# TSOC_GROVEY_GPIO.net
KiCad netlist of a schematic drawn in EAGLE
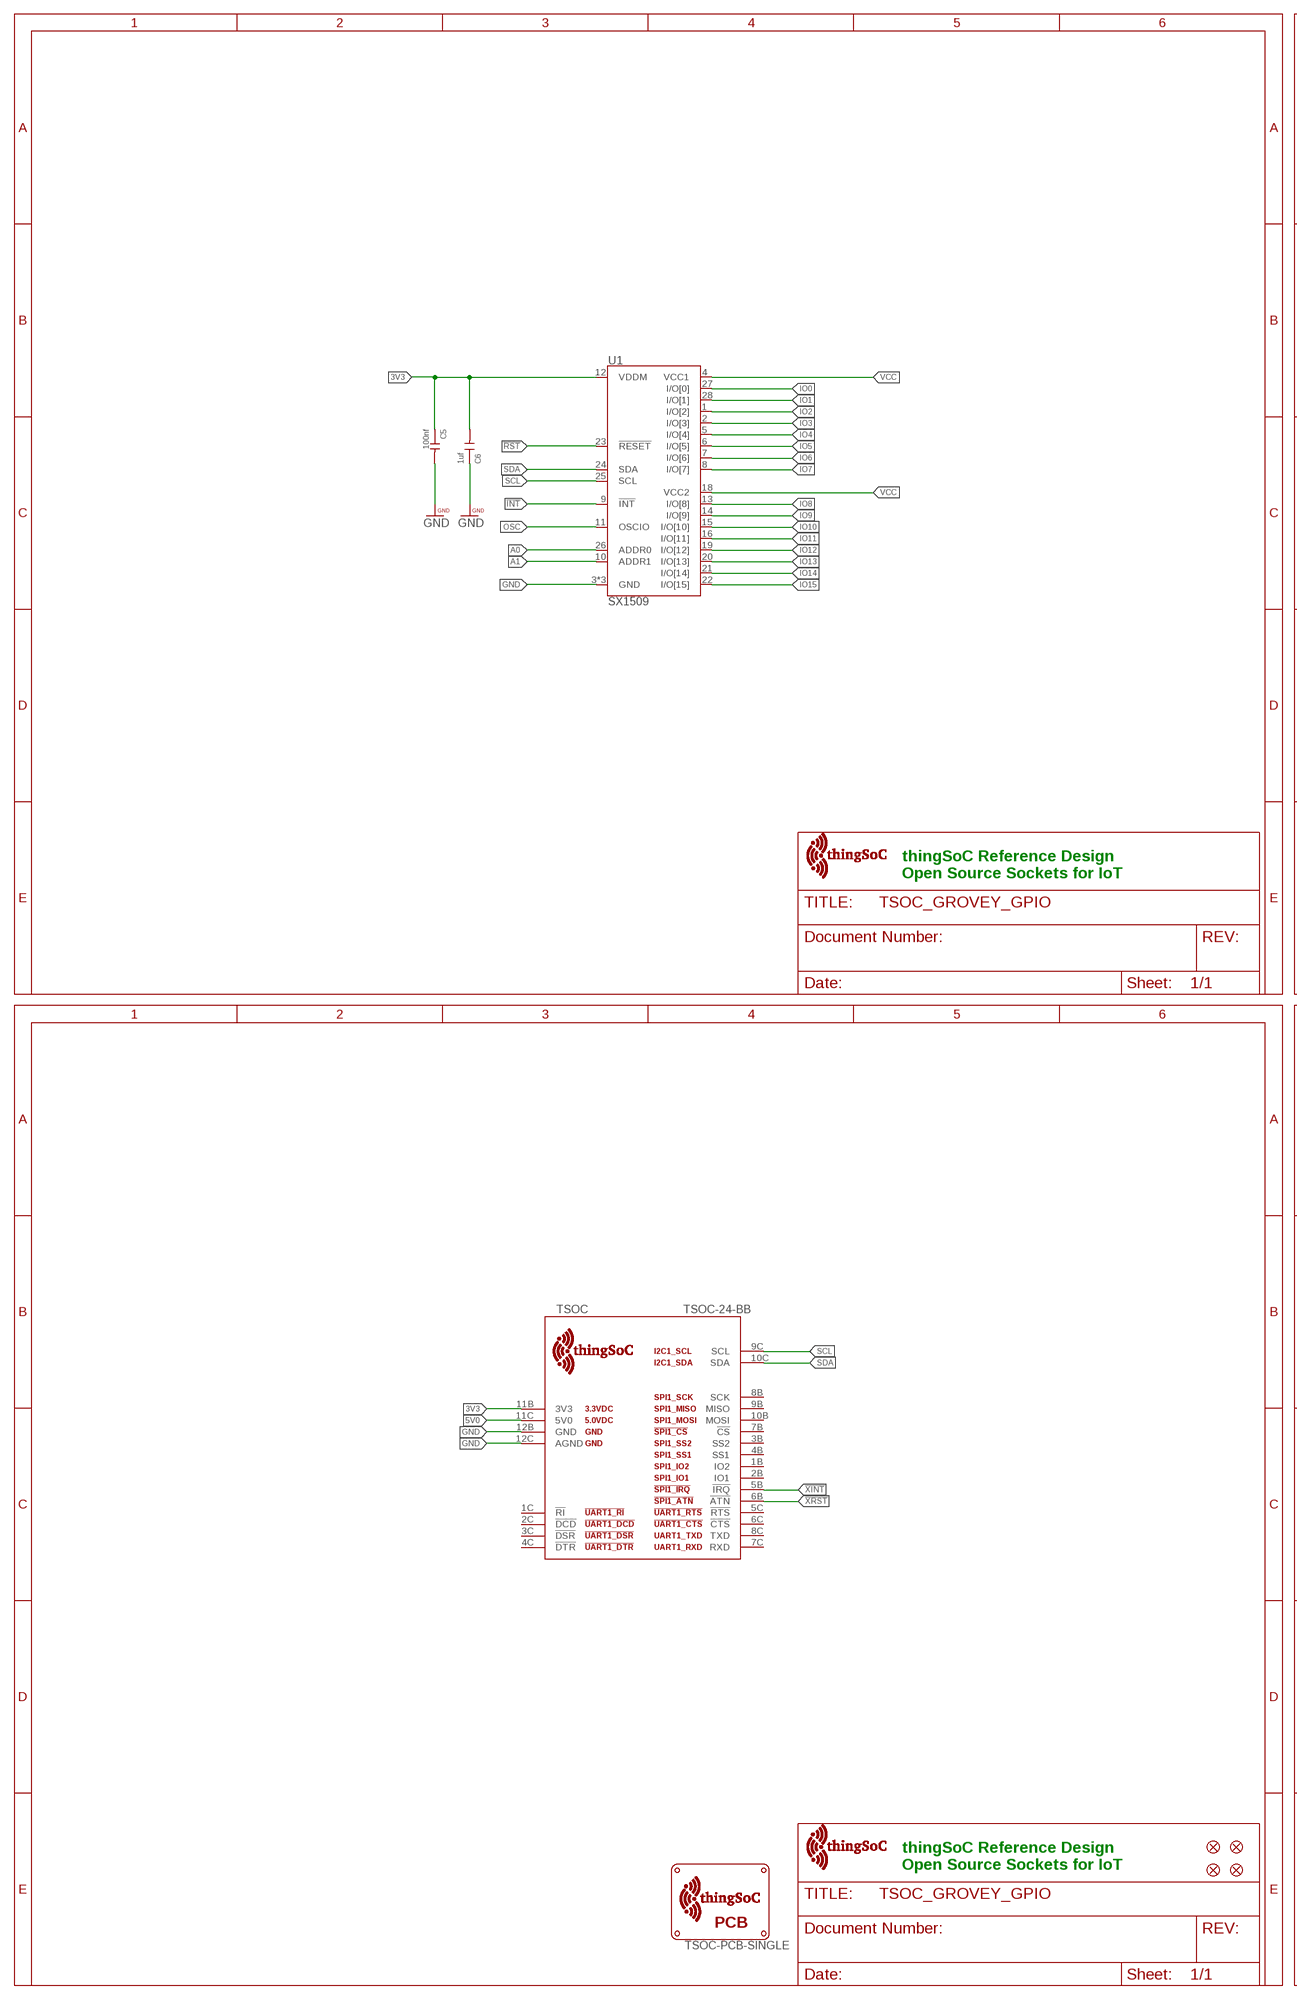
[diagram p0: schematic, sheet 1, part 1 of 2]
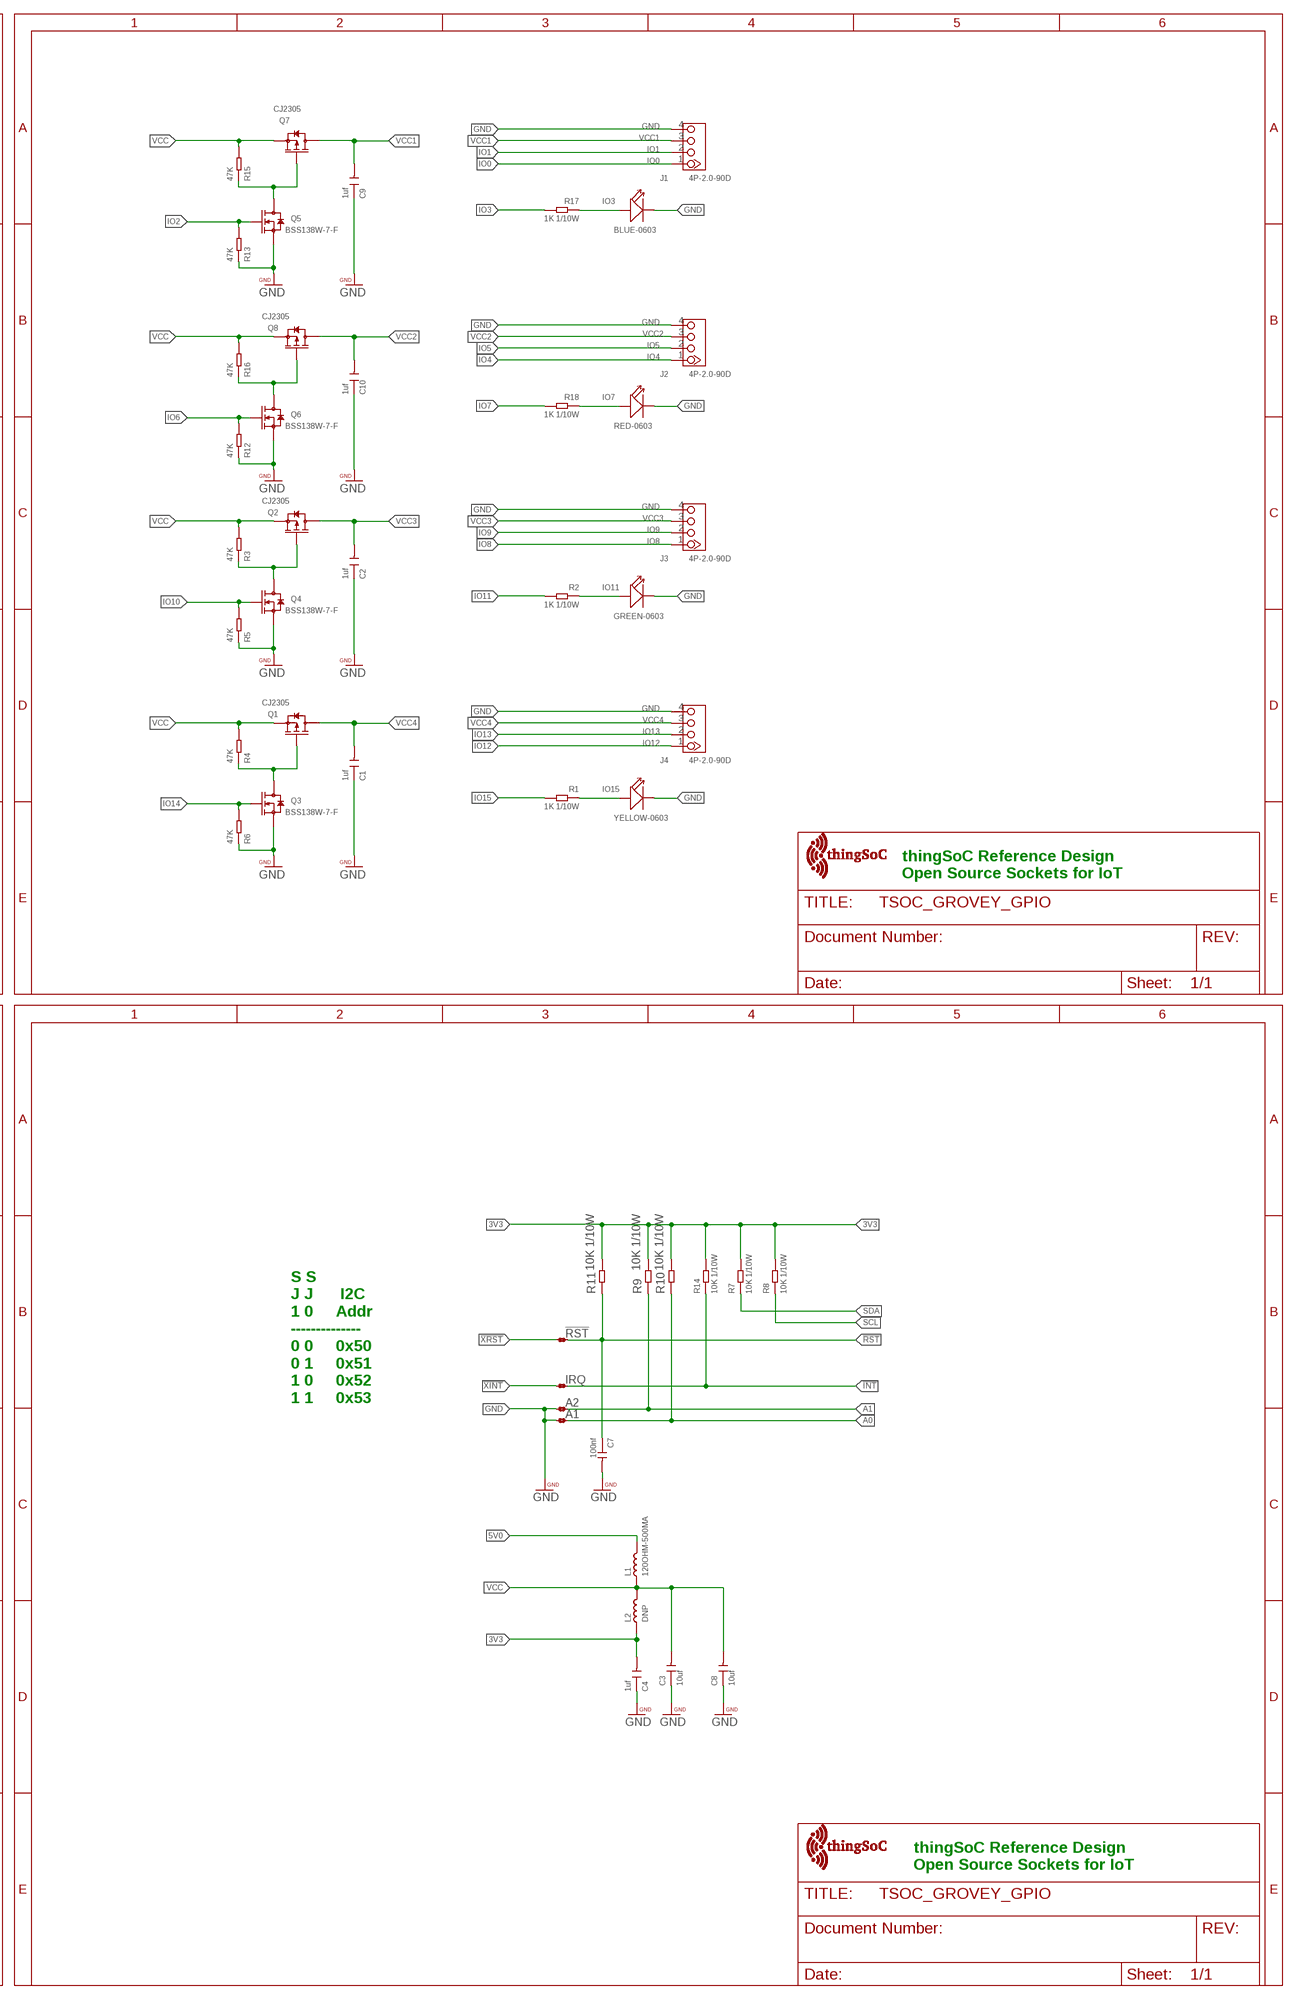
[diagram p1: schematic, sheet 1, part 2 of 2]

(export (version "E")
  (design (tool "Eeschema 10.0.6"))
  (components
    (comp (ref "!RST")
      (value "NO")
      (footprint "eagle-import:JMP-2-NO")
      (libsource (lib "eagle-import") (part "JMP-2-NO"))
    )
    (comp (ref "$$U$1")
      (value "TSOC-LOGO-SMALL")
      (footprint "eagle-import:TSOC-LOGO-SML")
      (libsource (lib "eagle-import") (part "TSOC-LOGO-SMALL"))
    )
    (comp (ref "$$U$2")
      (value "TSOC-LOGO-SMALL")
      (footprint "eagle-import:TSOC-LOGO-SML")
      (libsource (lib "eagle-import") (part "TSOC-LOGO-SMALL"))
    )
    (comp (ref "A1")
      (value "NO")
      (footprint "eagle-import:JMP-2-NO")
      (libsource (lib "eagle-import") (part "JMP-2-NO"))
    )
    (comp (ref "A2")
      (value "NO")
      (footprint "eagle-import:JMP-2-NO")
      (libsource (lib "eagle-import") (part "JMP-2-NO"))
    )
    (comp (ref "C1")
      (value "1uf")
      (footprint "eagle-import:C0603")
      (fields (field (name "MPN") "CC0603KRX7R8BB105"))
      (libsource (lib "eagle-import") (part "CERAMIC-1UF-25V-10%-X7R(0603)"))
    )
    (comp (ref "C2")
      (value "1uf")
      (footprint "eagle-import:C0603")
      (fields (field (name "MPN") "CC0603KRX7R8BB105"))
      (libsource (lib "eagle-import") (part "CERAMIC-1UF-25V-10%-X7R(0603)"))
    )
    (comp (ref "C3")
      (value "10uf")
      (footprint "eagle-import:C1206")
      (fields (field (name "MPN") "CC1206KKX5R8BB106"))
      (libsource (lib "eagle-import") (part "CERAMIC-10UF-25V-10%-X5R(1206)"))
    )
    (comp (ref "C4")
      (value "1uf")
      (footprint "eagle-import:C0603")
      (fields (field (name "MPN") "CC0603KRX7R8BB105"))
      (libsource (lib "eagle-import") (part "CERAMIC-1UF-25V-10%-X7R(0603)"))
    )
    (comp (ref "C5")
      (value "100nf")
      (footprint "eagle-import:C0603")
      (fields (field (name "MPN") "CC0603KRX7R9BB104"))
      (libsource (lib "eagle-import") (part "CERAMIC-100NF-50V-10%-X7R(0603)"))
    )
    (comp (ref "C6")
      (value "1uf")
      (footprint "eagle-import:C0603")
      (fields (field (name "MPN") "CC0603KRX7R8BB105"))
      (libsource (lib "eagle-import") (part "CERAMIC-1UF-25V-10%-X7R(0603)"))
    )
    (comp (ref "C7")
      (value "100nf")
      (footprint "eagle-import:C0603")
      (fields (field (name "MPN") "CC0603KRX7R9BB104"))
      (libsource (lib "eagle-import") (part "CERAMIC-100NF-50V-10%-X7R(0603)"))
    )
    (comp (ref "C8")
      (value "10uf")
      (footprint "eagle-import:C1206")
      (fields (field (name "MPN") "CC1206KKX5R8BB106"))
      (libsource (lib "eagle-import") (part "CERAMIC-10UF-25V-10%-X5R(1206)"))
    )
    (comp (ref "C9")
      (value "1uf")
      (footprint "eagle-import:C0603")
      (fields (field (name "MPN") "CC0603KRX7R8BB105"))
      (libsource (lib "eagle-import") (part "CERAMIC-1UF-25V-10%-X7R(0603)"))
    )
    (comp (ref "C10")
      (value "1uf")
      (footprint "eagle-import:C0603")
      (fields (field (name "MPN") "CC0603KRX7R8BB105"))
      (libsource (lib "eagle-import") (part "CERAMIC-1UF-25V-10%-X7R(0603)"))
    )
    (comp (ref "FID1")
      (value "FIDUCIALUFIDUCIAL")
      (footprint "eagle-import:MICRO-FIDUCIAL")
      (libsource (lib "eagle-import") (part "FIDUCIALUFIDUCIAL"))
    )
    (comp (ref "FID2")
      (value "FIDUCIALUFIDUCIAL")
      (footprint "eagle-import:MICRO-FIDUCIAL")
      (libsource (lib "eagle-import") (part "FIDUCIALUFIDUCIAL"))
    )
    (comp (ref "FID3")
      (value "FIDUCIALUFIDUCIAL")
      (footprint "eagle-import:MICRO-FIDUCIAL")
      (libsource (lib "eagle-import") (part "FIDUCIALUFIDUCIAL"))
    )
    (comp (ref "FID4")
      (value "FIDUCIALUFIDUCIAL")
      (footprint "eagle-import:MICRO-FIDUCIAL")
      (libsource (lib "eagle-import") (part "FIDUCIALUFIDUCIAL"))
    )
    (comp (ref "IO3")
      (value "BLUE-0603")
      (footprint "eagle-import:LED-0603")
      (fields (field (name "MPN") "19-217-BHC-ZL1M2RY-3T"))
      (libsource (lib "eagle-import") (part "SMD-LED-CLEAR-BLUE(0603)"))
    )
    (comp (ref "IO7")
      (value "RED-0603")
      (footprint "eagle-import:LED-0603")
      (fields (field (name "MPN") "19-217-R6C-AL1M2VY-3T"))
      (libsource (lib "eagle-import") (part "LED-SMD-RED-DIFFUSED(0603)"))
    )
    (comp (ref "IO11")
      (value "GREEN-0603")
      (footprint "eagle-import:LED-0603")
      (fields (field (name "MPN") "19-217-G7C-AN1P2-3T"))
      (libsource (lib "eagle-import") (part "SMD-LED-CLEAR-GREEN(0603)"))
    )
    (comp (ref "IO15")
      (value "YELLOW-0603")
      (footprint "eagle-import:LED-0603")
      (fields (field (name "MPN") "19-217-Y5C-AM1N1VY-3T"))
      (libsource (lib "eagle-import") (part "SMD-LED-CLEAR-YELLOW(0603)"))
    )
    (comp (ref "IRQ")
      (value "NO")
      (footprint "eagle-import:JMP-2-NO")
      (libsource (lib "eagle-import") (part "JMP-2-NO"))
    )
    (comp (ref "J1")
      (value "4P-2.0-90D")
      (footprint "eagle-import:HW4-2.0-90D")
      (libsource (lib "eagle-import") (part "GROVE-CONNECTOR-DIP-90D(4P-2.0)"))
    )
    (comp (ref "J2")
      (value "4P-2.0-90D")
      (footprint "eagle-import:HW4-2.0-90D")
      (libsource (lib "eagle-import") (part "GROVE-CONNECTOR-DIP-90D(4P-2.0)"))
    )
    (comp (ref "J3")
      (value "4P-2.0-90D")
      (footprint "eagle-import:HW4-2.0-90D")
      (libsource (lib "eagle-import") (part "GROVE-CONNECTOR-DIP-90D(4P-2.0)"))
    )
    (comp (ref "J4")
      (value "4P-2.0-90D")
      (footprint "eagle-import:HW4-2.0-90D")
      (libsource (lib "eagle-import") (part "GROVE-CONNECTOR-DIP-90D(4P-2.0)"))
    )
    (comp (ref "L1")
      (value "120OHM-500MA")
      (footprint "eagle-import:L0603")
      (fields (field (name "MPN") "BLM18AG121SN1D"))
      (libsource (lib "eagle-import") (part "SMD-FERRITE-CHIP-120-OHM-500MA(0603)"))
    )
    (comp (ref "L2")
      (value "DNP")
      (footprint "eagle-import:L0603")
      (fields (field (name "MPN") "BLM18AG121SN1D"))
      (libsource (lib "eagle-import") (part "SMD-FERRITE-CHIP-120-OHM-500MA(0603)"))
    )
    (comp (ref "Q1")
      (value "CJ2305")
      (footprint "eagle-import:SOT-23")
      (libsource (lib "eagle-import") (part "SMD-MOSFET-P-CH-8V-4.1A-CJ2305(SOT-23)"))
    )
    (comp (ref "Q2")
      (value "CJ2305")
      (footprint "eagle-import:SOT-23")
      (libsource (lib "eagle-import") (part "SMD-MOSFET-P-CH-8V-4.1A-CJ2305(SOT-23)"))
    )
    (comp (ref "Q3")
      (value "BSS138W-7-F")
      (footprint "eagle-import:SOT-23")
      (libsource (lib "eagle-import") (part "SMD-MOSFET-N-CH-50V-200MA-BSS138W-7-F(SOT-23)"))
    )
    (comp (ref "Q4")
      (value "BSS138W-7-F")
      (footprint "eagle-import:SOT-23")
      (libsource (lib "eagle-import") (part "SMD-MOSFET-N-CH-50V-200MA-BSS138W-7-F(SOT-23)"))
    )
    (comp (ref "Q5")
      (value "BSS138W-7-F")
      (footprint "eagle-import:SOT-23")
      (libsource (lib "eagle-import") (part "SMD-MOSFET-N-CH-50V-200MA-BSS138W-7-F(SOT-23)"))
    )
    (comp (ref "Q6")
      (value "BSS138W-7-F")
      (footprint "eagle-import:SOT-23")
      (libsource (lib "eagle-import") (part "SMD-MOSFET-N-CH-50V-200MA-BSS138W-7-F(SOT-23)"))
    )
    (comp (ref "Q7")
      (value "CJ2305")
      (footprint "eagle-import:SOT-23")
      (libsource (lib "eagle-import") (part "SMD-MOSFET-P-CH-8V-4.1A-CJ2305(SOT-23)"))
    )
    (comp (ref "Q8")
      (value "CJ2305")
      (footprint "eagle-import:SOT-23")
      (libsource (lib "eagle-import") (part "SMD-MOSFET-P-CH-8V-4.1A-CJ2305(SOT-23)"))
    )
    (comp (ref "R1")
      (value "1K 1/10W")
      (footprint "eagle-import:R0603")
      (fields (field (name "MPN") "RC0603JR-071KL"))
      (libsource (lib "eagle-import") (part "SMD-RES-1K-5%-1/10W(0603)"))
    )
    (comp (ref "R2")
      (value "1K 1/10W")
      (footprint "eagle-import:R0603")
      (fields (field (name "MPN") "RC0603JR-071KL"))
      (libsource (lib "eagle-import") (part "SMD-RES-1K-5%-1/10W(0603)"))
    )
    (comp (ref "R3")
      (value "47K")
      (footprint "eagle-import:R0603")
      (fields (field (name "MPN") "RC0603JR-0747KL"))
      (libsource (lib "eagle-import") (part "SMD-RES-47K-5%-1/10W(0603)"))
    )
    (comp (ref "R4")
      (value "47K")
      (footprint "eagle-import:R0603")
      (fields (field (name "MPN") "RC0603JR-0747KL"))
      (libsource (lib "eagle-import") (part "SMD-RES-47K-5%-1/10W(0603)"))
    )
    (comp (ref "R5")
      (value "47K")
      (footprint "eagle-import:R0603")
      (fields (field (name "MPN") "RC0603JR-0747KL"))
      (libsource (lib "eagle-import") (part "SMD-RES-47K-5%-1/10W(0603)"))
    )
    (comp (ref "R6")
      (value "47K")
      (footprint "eagle-import:R0603")
      (fields (field (name "MPN") "RC0603JR-0747KL"))
      (libsource (lib "eagle-import") (part "SMD-RES-47K-5%-1/10W(0603)"))
    )
    (comp (ref "R7")
      (value "10K 1/10W")
      (footprint "eagle-import:R0603")
      (fields (field (name "MPN") "RC0603JR-0710KL"))
      (libsource (lib "eagle-import") (part "SMD-RES-10K-5%-1/10W(0603)"))
    )
    (comp (ref "R8")
      (value "10K 1/10W")
      (footprint "eagle-import:R0603")
      (fields (field (name "MPN") "RC0603JR-0710KL"))
      (libsource (lib "eagle-import") (part "SMD-RES-10K-5%-1/10W(0603)"))
    )
    (comp (ref "R9")
      (value "10K 1/10W")
      (footprint "eagle-import:R0603")
      (fields (field (name "MPN") "RC0603JR-0710KL"))
      (libsource (lib "eagle-import") (part "SMD-RES-10K-5%-1/10W(0603)"))
    )
    (comp (ref "R10")
      (value "10K 1/10W")
      (footprint "eagle-import:R0603")
      (fields (field (name "MPN") "RC0603JR-0710KL"))
      (libsource (lib "eagle-import") (part "SMD-RES-10K-5%-1/10W(0603)"))
    )
    (comp (ref "R11")
      (value "10K 1/10W")
      (footprint "eagle-import:R0603")
      (fields (field (name "MPN") "RC0603JR-0710KL"))
      (libsource (lib "eagle-import") (part "SMD-RES-10K-5%-1/10W(0603)"))
    )
    (comp (ref "R12")
      (value "47K")
      (footprint "eagle-import:R0603")
      (fields (field (name "MPN") "RC0603JR-0747KL"))
      (libsource (lib "eagle-import") (part "SMD-RES-47K-5%-1/10W(0603)"))
    )
    (comp (ref "R13")
      (value "47K")
      (footprint "eagle-import:R0603")
      (fields (field (name "MPN") "RC0603JR-0747KL"))
      (libsource (lib "eagle-import") (part "SMD-RES-47K-5%-1/10W(0603)"))
    )
    (comp (ref "R14")
      (value "10K 1/10W")
      (footprint "eagle-import:R0603")
      (fields (field (name "MPN") "RC0603JR-0710KL"))
      (libsource (lib "eagle-import") (part "SMD-RES-10K-5%-1/10W(0603)"))
    )
    (comp (ref "R15")
      (value "47K")
      (footprint "eagle-import:R0603")
      (fields (field (name "MPN") "RC0603JR-0747KL"))
      (libsource (lib "eagle-import") (part "SMD-RES-47K-5%-1/10W(0603)"))
    )
    (comp (ref "R16")
      (value "47K")
      (footprint "eagle-import:R0603")
      (fields (field (name "MPN") "RC0603JR-0747KL"))
      (libsource (lib "eagle-import") (part "SMD-RES-47K-5%-1/10W(0603)"))
    )
    (comp (ref "R17")
      (value "1K 1/10W")
      (footprint "eagle-import:R0603")
      (fields (field (name "MPN") "RC0603JR-071KL"))
      (libsource (lib "eagle-import") (part "SMD-RES-1K-5%-1/10W(0603)"))
    )
    (comp (ref "R18")
      (value "1K 1/10W")
      (footprint "eagle-import:R0603")
      (fields (field (name "MPN") "RC0603JR-071KL"))
      (libsource (lib "eagle-import") (part "SMD-RES-1K-5%-1/10W(0603)"))
    )
    (comp (ref "TSOC")
      (value "TSOC-24-BB")
      (footprint "eagle-import:TSOC-BB-S24")
      (libsource (lib "eagle-import") (part "TSOC-24-BB"))
    )
    (comp (ref "U$3")
      (value "TSOC-PCB-SINGLE")
      (footprint "eagle-import:TSOC-BB-BRD-DIM")
      (libsource (lib "eagle-import") (part "TSOC-PCB-SINGLE"))
    )
    (comp (ref "U$101")
      (value "TSOC-LOGO-LRG")
      (footprint "eagle-import:TSOC-LOGO-LRG")
      (libsource (lib "eagle-import") (part "TSOC-LOGO-LRG"))
    )
    (comp (ref "U$102")
      (value "TSOC-LOGO-SMALL")
      (footprint "eagle-import:TSOC-LOGO-SML")
      (libsource (lib "eagle-import") (part "TSOC-LOGO-SMALL"))
    )
    (comp (ref "U1")
      (value "SX1509")
      (footprint "eagle-import:QFN-28")
      (libsource (lib "eagle-import") (part "SX1509"))
    )
  )
  (nets
    (net (code "1") (name "/~{INT}") (class "Default")
      (node (ref "IRQ") (pin "2") (pinfunction "2_2") (pintype "passive"))
      (node (ref "R14") (pin "1") (pinfunction "1_1") (pintype "passive"))
      (node (ref "U1") (pin "9") (pinfunction "~{INT}_9") (pintype "bidirectional"))
    )
    (net (code "2") (name "/~{RST}") (class "Default")
      (node (ref "!RST") (pin "1") (pinfunction "1_1") (pintype "passive"))
      (node (ref "C7") (pin "1") (pinfunction "1_1") (pintype "passive"))
      (node (ref "R11") (pin "1") (pinfunction "1_1") (pintype "passive"))
      (node (ref "U1") (pin "23") (pinfunction "~{RESET}_23") (pintype "bidirectional"))
    )
    (net (code "3") (name "/~{XINT}") (class "Default")
      (node (ref "IRQ") (pin "1") (pinfunction "1_1") (pintype "passive"))
      (node (ref "TSOC") (pin "5B") (pinfunction "~{IRQ}_5B") (pintype "bidirectional"))
    )
    (net (code "4") (name "/~{XRST}") (class "Default")
      (node (ref "!RST") (pin "2") (pinfunction "2_2") (pintype "passive"))
      (node (ref "TSOC") (pin "6B") (pinfunction "~{ATN}_6B") (pintype "bidirectional"))
    )
    (net (code "5") (name "3V3") (class "Default")
      (node (ref "C4") (pin "2") (pinfunction "2_2") (pintype "passive"))
      (node (ref "C5") (pin "1") (pinfunction "1_1") (pintype "passive"))
      (node (ref "C6") (pin "2") (pinfunction "2_2") (pintype "passive"))
      (node (ref "L2") (pin "1") (pinfunction "1_1") (pintype "passive"))
      (node (ref "R10") (pin "2") (pinfunction "2_2") (pintype "passive"))
      (node (ref "R11") (pin "2") (pinfunction "2_2") (pintype "passive"))
      (node (ref "R14") (pin "2") (pinfunction "2_2") (pintype "passive"))
      (node (ref "R7") (pin "2") (pinfunction "2_2") (pintype "passive"))
      (node (ref "R8") (pin "2") (pinfunction "2_2") (pintype "passive"))
      (node (ref "R9") (pin "2") (pinfunction "2_2") (pintype "passive"))
      (node (ref "TSOC") (pin "11B") (pinfunction "3V3_11B") (pintype "bidirectional"))
      (node (ref "U1") (pin "12") (pinfunction "VDDM_12") (pintype "bidirectional"))
    )
    (net (code "6") (name "5V0") (class "Default")
      (node (ref "L1") (pin "2") (pinfunction "2_2") (pintype "passive"))
      (node (ref "TSOC") (pin "11C") (pinfunction "5V0_11C") (pintype "bidirectional"))
    )
    (net (code "7") (name "A0") (class "Default")
      (node (ref "A1") (pin "2") (pinfunction "2_2") (pintype "passive"))
      (node (ref "R10") (pin "1") (pinfunction "1_1") (pintype "passive"))
      (node (ref "U1") (pin "26") (pinfunction "ADDR0_26") (pintype "bidirectional"))
    )
    (net (code "8") (name "A1") (class "Default")
      (node (ref "A2") (pin "2") (pinfunction "2_2") (pintype "passive"))
      (node (ref "R9") (pin "1") (pinfunction "1_1") (pintype "passive"))
      (node (ref "U1") (pin "10") (pinfunction "ADDR1_10") (pintype "bidirectional"))
    )
    (net (code "9") (name "GND") (class "Default")
      (node (ref "A1") (pin "1") (pinfunction "1_1") (pintype "passive"))
      (node (ref "A2") (pin "1") (pinfunction "1_1") (pintype "passive"))
      (node (ref "C1") (pin "1") (pinfunction "1_1") (pintype "passive"))
      (node (ref "C10") (pin "1") (pinfunction "1_1") (pintype "passive"))
      (node (ref "C2") (pin "1") (pinfunction "1_1") (pintype "passive"))
      (node (ref "C3") (pin "1") (pinfunction "1_1") (pintype "passive"))
      (node (ref "C4") (pin "1") (pinfunction "1_1") (pintype "passive"))
      (node (ref "C5") (pin "2") (pinfunction "2_2") (pintype "passive"))
      (node (ref "C6") (pin "1") (pinfunction "1_1") (pintype "passive"))
      (node (ref "C7") (pin "2") (pinfunction "2_2") (pintype "passive"))
      (node (ref "C8") (pin "1") (pinfunction "1_1") (pintype "passive"))
      (node (ref "C9") (pin "1") (pinfunction "1_1") (pintype "passive"))
      (node (ref "IO11") (pin "-") (pinfunction "-_-") (pintype "passive"))
      (node (ref "IO15") (pin "-") (pinfunction "-_-") (pintype "passive"))
      (node (ref "IO3") (pin "-") (pinfunction "-_-") (pintype "passive"))
      (node (ref "IO7") (pin "-") (pinfunction "-_-") (pintype "passive"))
      (node (ref "J1") (pin "4") (pinfunction "4_4") (pintype "bidirectional"))
      (node (ref "J2") (pin "4") (pinfunction "4_4") (pintype "bidirectional"))
      (node (ref "J3") (pin "4") (pinfunction "4_4") (pintype "bidirectional"))
      (node (ref "J4") (pin "4") (pinfunction "4_4") (pintype "bidirectional"))
      (node (ref "Q3") (pin "2") (pinfunction "S_2") (pintype "passive"))
      (node (ref "Q4") (pin "2") (pinfunction "S_2") (pintype "passive"))
      (node (ref "Q5") (pin "2") (pinfunction "S_2") (pintype "passive"))
      (node (ref "Q6") (pin "2") (pinfunction "S_2") (pintype "passive"))
      (node (ref "R12") (pin "1") (pinfunction "1_1") (pintype "passive"))
      (node (ref "R13") (pin "1") (pinfunction "1_1") (pintype "passive"))
      (node (ref "R5") (pin "1") (pinfunction "1_1") (pintype "passive"))
      (node (ref "R6") (pin "1") (pinfunction "1_1") (pintype "passive"))
      (node (ref "TSOC") (pin "12B") (pinfunction "GND_12B") (pintype "bidirectional"))
      (node (ref "TSOC") (pin "12C") (pinfunction "AGND_12C") (pintype "bidirectional"))
      (node (ref "U1") (pin "17") (pinfunction "GND_17") (pintype "bidirectional"))
      (node (ref "U1") (pin "29") (pinfunction "GND_29") (pintype "bidirectional"))
      (node (ref "U1") (pin "3") (pinfunction "GND_3") (pintype "bidirectional"))
    )
    (net (code "10") (name "IO0") (class "Default")
      (node (ref "J1") (pin "1") (pinfunction "1_1") (pintype "bidirectional"))
      (node (ref "U1") (pin "27") (pinfunction "I/O[0]_27") (pintype "bidirectional"))
    )
    (net (code "11") (name "IO1") (class "Default")
      (node (ref "J1") (pin "2") (pinfunction "2_2") (pintype "bidirectional"))
      (node (ref "U1") (pin "28") (pinfunction "I/O[1]_28") (pintype "bidirectional"))
    )
    (net (code "12") (name "IO2") (class "Default")
      (node (ref "Q5") (pin "1") (pinfunction "G_1") (pintype "passive"))
      (node (ref "R13") (pin "2") (pinfunction "2_2") (pintype "passive"))
      (node (ref "U1") (pin "1") (pinfunction "I/O[2]_1") (pintype "bidirectional"))
    )
    (net (code "13") (name "IO3") (class "Default")
      (node (ref "R17") (pin "2") (pinfunction "2_2") (pintype "passive"))
      (node (ref "U1") (pin "2") (pinfunction "I/O[3]_2") (pintype "bidirectional"))
    )
    (net (code "14") (name "IO4") (class "Default")
      (node (ref "J2") (pin "1") (pinfunction "1_1") (pintype "bidirectional"))
      (node (ref "U1") (pin "5") (pinfunction "I/O[4]_5") (pintype "bidirectional"))
    )
    (net (code "15") (name "IO5") (class "Default")
      (node (ref "J2") (pin "2") (pinfunction "2_2") (pintype "bidirectional"))
      (node (ref "U1") (pin "6") (pinfunction "I/O[5]_6") (pintype "bidirectional"))
    )
    (net (code "16") (name "IO6") (class "Default")
      (node (ref "Q6") (pin "1") (pinfunction "G_1") (pintype "passive"))
      (node (ref "R12") (pin "2") (pinfunction "2_2") (pintype "passive"))
      (node (ref "U1") (pin "7") (pinfunction "I/O[6]_7") (pintype "bidirectional"))
    )
    (net (code "17") (name "IO7") (class "Default")
      (node (ref "R18") (pin "2") (pinfunction "2_2") (pintype "passive"))
      (node (ref "U1") (pin "8") (pinfunction "I/O[7]_8") (pintype "bidirectional"))
    )
    (net (code "18") (name "IO8") (class "Default")
      (node (ref "J3") (pin "1") (pinfunction "1_1") (pintype "bidirectional"))
      (node (ref "U1") (pin "13") (pinfunction "I/O[8]_13") (pintype "bidirectional"))
    )
    (net (code "19") (name "IO9") (class "Default")
      (node (ref "J3") (pin "2") (pinfunction "2_2") (pintype "bidirectional"))
      (node (ref "U1") (pin "14") (pinfunction "I/O[9]_14") (pintype "bidirectional"))
    )
    (net (code "20") (name "IO10") (class "Default")
      (node (ref "Q4") (pin "1") (pinfunction "G_1") (pintype "passive"))
      (node (ref "R5") (pin "2") (pinfunction "2_2") (pintype "passive"))
      (node (ref "U1") (pin "15") (pinfunction "I/O[10]_15") (pintype "bidirectional"))
    )
    (net (code "21") (name "IO11") (class "Default")
      (node (ref "R2") (pin "2") (pinfunction "2_2") (pintype "passive"))
      (node (ref "U1") (pin "16") (pinfunction "I/O[11]_16") (pintype "bidirectional"))
    )
    (net (code "22") (name "IO12") (class "Default")
      (node (ref "J4") (pin "1") (pinfunction "1_1") (pintype "bidirectional"))
      (node (ref "U1") (pin "19") (pinfunction "I/O[12]_19") (pintype "bidirectional"))
    )
    (net (code "23") (name "IO13") (class "Default")
      (node (ref "J4") (pin "2") (pinfunction "2_2") (pintype "bidirectional"))
      (node (ref "U1") (pin "20") (pinfunction "I/O[13]_20") (pintype "bidirectional"))
    )
    (net (code "24") (name "IO14") (class "Default")
      (node (ref "Q3") (pin "1") (pinfunction "G_1") (pintype "passive"))
      (node (ref "R6") (pin "2") (pinfunction "2_2") (pintype "passive"))
      (node (ref "U1") (pin "21") (pinfunction "I/O[14]_21") (pintype "bidirectional"))
    )
    (net (code "25") (name "IO15") (class "Default")
      (node (ref "R1") (pin "2") (pinfunction "2_2") (pintype "passive"))
      (node (ref "U1") (pin "22") (pinfunction "I/O[15]_22") (pintype "bidirectional"))
    )
    (net (code "26") (name "Net-(IO3-Pad+)") (class "Default")
      (node (ref "IO3") (pin "+") (pinfunction "+_+") (pintype "passive"))
      (node (ref "R17") (pin "1") (pinfunction "1_1") (pintype "passive"))
    )
    (net (code "27") (name "Net-(IO7-Pad+)") (class "Default")
      (node (ref "IO7") (pin "+") (pinfunction "+_+") (pintype "passive"))
      (node (ref "R18") (pin "1") (pinfunction "1_1") (pintype "passive"))
    )
    (net (code "28") (name "Net-(IO11-Pad+)") (class "Default")
      (node (ref "IO11") (pin "+") (pinfunction "+_+") (pintype "passive"))
      (node (ref "R2") (pin "1") (pinfunction "1_1") (pintype "passive"))
    )
    (net (code "29") (name "Net-(IO15-Pad+)") (class "Default")
      (node (ref "IO15") (pin "+") (pinfunction "+_+") (pintype "passive"))
      (node (ref "R1") (pin "1") (pinfunction "1_1") (pintype "passive"))
    )
    (net (code "30") (name "Net-(Q1-G)") (class "Default")
      (node (ref "Q1") (pin "1") (pinfunction "G_1") (pintype "passive"))
      (node (ref "Q3") (pin "3") (pinfunction "D_3") (pintype "passive"))
      (node (ref "R4") (pin "1") (pinfunction "1_1") (pintype "passive"))
    )
    (net (code "31") (name "Net-(Q2-G)") (class "Default")
      (node (ref "Q2") (pin "1") (pinfunction "G_1") (pintype "passive"))
      (node (ref "Q4") (pin "3") (pinfunction "D_3") (pintype "passive"))
      (node (ref "R3") (pin "1") (pinfunction "1_1") (pintype "passive"))
    )
    (net (code "32") (name "Net-(Q5-D)") (class "Default")
      (node (ref "Q5") (pin "3") (pinfunction "D_3") (pintype "passive"))
      (node (ref "Q7") (pin "1") (pinfunction "G_1") (pintype "passive"))
      (node (ref "R15") (pin "1") (pinfunction "1_1") (pintype "passive"))
    )
    (net (code "33") (name "Net-(Q6-D)") (class "Default")
      (node (ref "Q6") (pin "3") (pinfunction "D_3") (pintype "passive"))
      (node (ref "Q8") (pin "1") (pinfunction "G_1") (pintype "passive"))
      (node (ref "R16") (pin "1") (pinfunction "1_1") (pintype "passive"))
    )
    (net (code "34") (name "OSC") (class "Default")
      (node (ref "U1") (pin "11") (pinfunction "OSCIO_11") (pintype "bidirectional"))
    )
    (net (code "35") (name "SCL") (class "Default")
      (node (ref "R8") (pin "1") (pinfunction "1_1") (pintype "passive"))
      (node (ref "TSOC") (pin "9C") (pinfunction "SCL_9C") (pintype "bidirectional"))
      (node (ref "U1") (pin "25") (pinfunction "SCL_25") (pintype "bidirectional"))
    )
    (net (code "36") (name "SDA") (class "Default")
      (node (ref "R7") (pin "1") (pinfunction "1_1") (pintype "passive"))
      (node (ref "TSOC") (pin "10C") (pinfunction "SDA_10C") (pintype "bidirectional"))
      (node (ref "U1") (pin "24") (pinfunction "SDA_24") (pintype "bidirectional"))
    )
    (net (code "37") (name "VCC") (class "Default")
      (node (ref "C3") (pin "2") (pinfunction "2_2") (pintype "passive"))
      (node (ref "C8") (pin "2") (pinfunction "2_2") (pintype "passive"))
      (node (ref "L1") (pin "1") (pinfunction "1_1") (pintype "passive"))
      (node (ref "L2") (pin "2") (pinfunction "2_2") (pintype "passive"))
      (node (ref "Q1") (pin "2") (pinfunction "S_2") (pintype "passive"))
      (node (ref "Q2") (pin "2") (pinfunction "S_2") (pintype "passive"))
      (node (ref "Q7") (pin "2") (pinfunction "S_2") (pintype "passive"))
      (node (ref "Q8") (pin "2") (pinfunction "S_2") (pintype "passive"))
      (node (ref "R15") (pin "2") (pinfunction "2_2") (pintype "passive"))
      (node (ref "R16") (pin "2") (pinfunction "2_2") (pintype "passive"))
      (node (ref "R3") (pin "2") (pinfunction "2_2") (pintype "passive"))
      (node (ref "R4") (pin "2") (pinfunction "2_2") (pintype "passive"))
      (node (ref "U1") (pin "18") (pinfunction "VCC2_18") (pintype "bidirectional"))
      (node (ref "U1") (pin "4") (pinfunction "VCC1_4") (pintype "bidirectional"))
    )
    (net (code "38") (name "VCC1") (class "Default")
      (node (ref "C9") (pin "2") (pinfunction "2_2") (pintype "passive"))
      (node (ref "J1") (pin "3") (pinfunction "3_3") (pintype "bidirectional"))
      (node (ref "Q7") (pin "3") (pinfunction "D_3") (pintype "passive"))
    )
    (net (code "39") (name "VCC2") (class "Default")
      (node (ref "C10") (pin "2") (pinfunction "2_2") (pintype "passive"))
      (node (ref "J2") (pin "3") (pinfunction "3_3") (pintype "bidirectional"))
      (node (ref "Q8") (pin "3") (pinfunction "D_3") (pintype "passive"))
    )
    (net (code "40") (name "VCC3") (class "Default")
      (node (ref "C2") (pin "2") (pinfunction "2_2") (pintype "passive"))
      (node (ref "J3") (pin "3") (pinfunction "3_3") (pintype "bidirectional"))
      (node (ref "Q2") (pin "3") (pinfunction "D_3") (pintype "passive"))
    )
    (net (code "41") (name "VCC4") (class "Default")
      (node (ref "C1") (pin "2") (pinfunction "2_2") (pintype "passive"))
      (node (ref "J4") (pin "3") (pinfunction "3_3") (pintype "bidirectional"))
      (node (ref "Q1") (pin "3") (pinfunction "D_3") (pintype "passive"))
    )
    (net (code "42") (name "unconnected-(TSOC-IO1-Pad2B)") (class "Default")
      (node (ref "TSOC") (pin "2B") (pinfunction "IO1_2B") (pintype "bidirectional"))
    )
    (net (code "43") (name "unconnected-(TSOC-IO2-Pad1B)") (class "Default")
      (node (ref "TSOC") (pin "1B") (pinfunction "IO2_1B") (pintype "bidirectional"))
    )
    (net (code "44") (name "unconnected-(TSOC-MISO-Pad9B)") (class "Default")
      (node (ref "TSOC") (pin "9B") (pinfunction "MISO_9B") (pintype "bidirectional"))
    )
    (net (code "45") (name "unconnected-(TSOC-MOSI-Pad10B)") (class "Default")
      (node (ref "TSOC") (pin "10B") (pinfunction "MOSI_10B") (pintype "bidirectional"))
    )
    (net (code "46") (name "unconnected-(TSOC-RXD-Pad7C)") (class "Default")
      (node (ref "TSOC") (pin "7C") (pinfunction "RXD_7C") (pintype "bidirectional"))
    )
    (net (code "47") (name "unconnected-(TSOC-SCK-Pad8B)") (class "Default")
      (node (ref "TSOC") (pin "8B") (pinfunction "SCK_8B") (pintype "bidirectional"))
    )
    (net (code "48") (name "unconnected-(TSOC-SS1-Pad4B)") (class "Default")
      (node (ref "TSOC") (pin "4B") (pinfunction "SS1_4B") (pintype "bidirectional"))
    )
    (net (code "49") (name "unconnected-(TSOC-SS2-Pad3B)") (class "Default")
      (node (ref "TSOC") (pin "3B") (pinfunction "SS2_3B") (pintype "bidirectional"))
    )
    (net (code "50") (name "unconnected-(TSOC-TXD-Pad8C)") (class "Default")
      (node (ref "TSOC") (pin "8C") (pinfunction "TXD_8C") (pintype "bidirectional"))
    )
    (net (code "51") (name "unconnected-(TSOC-~{CS}-Pad7B)") (class "Default")
      (node (ref "TSOC") (pin "7B") (pinfunction "~{CS}_7B") (pintype "bidirectional"))
    )
    (net (code "52") (name "unconnected-(TSOC-~{CTS}-Pad6C)") (class "Default")
      (node (ref "TSOC") (pin "6C") (pinfunction "~{CTS}_6C") (pintype "bidirectional"))
    )
    (net (code "53") (name "unconnected-(TSOC-~{DCD}-Pad2C)") (class "Default")
      (node (ref "TSOC") (pin "2C") (pinfunction "~{DCD}_2C") (pintype "bidirectional"))
    )
    (net (code "54") (name "unconnected-(TSOC-~{DSR}-Pad3C)") (class "Default")
      (node (ref "TSOC") (pin "3C") (pinfunction "~{DSR}_3C") (pintype "bidirectional"))
    )
    (net (code "55") (name "unconnected-(TSOC-~{DTR}-Pad4C)") (class "Default")
      (node (ref "TSOC") (pin "4C") (pinfunction "~{DTR}_4C") (pintype "bidirectional"))
    )
    (net (code "56") (name "unconnected-(TSOC-~{RI}-Pad1C)") (class "Default")
      (node (ref "TSOC") (pin "1C") (pinfunction "~{RI}_1C") (pintype "bidirectional"))
    )
    (net (code "57") (name "unconnected-(TSOC-~{RTS}-Pad5C)") (class "Default")
      (node (ref "TSOC") (pin "5C") (pinfunction "~{RTS}_5C") (pintype "bidirectional"))
    )
  )
)
